# ESP.net
KiCad netlist of a schematic drawn in Altium Designer
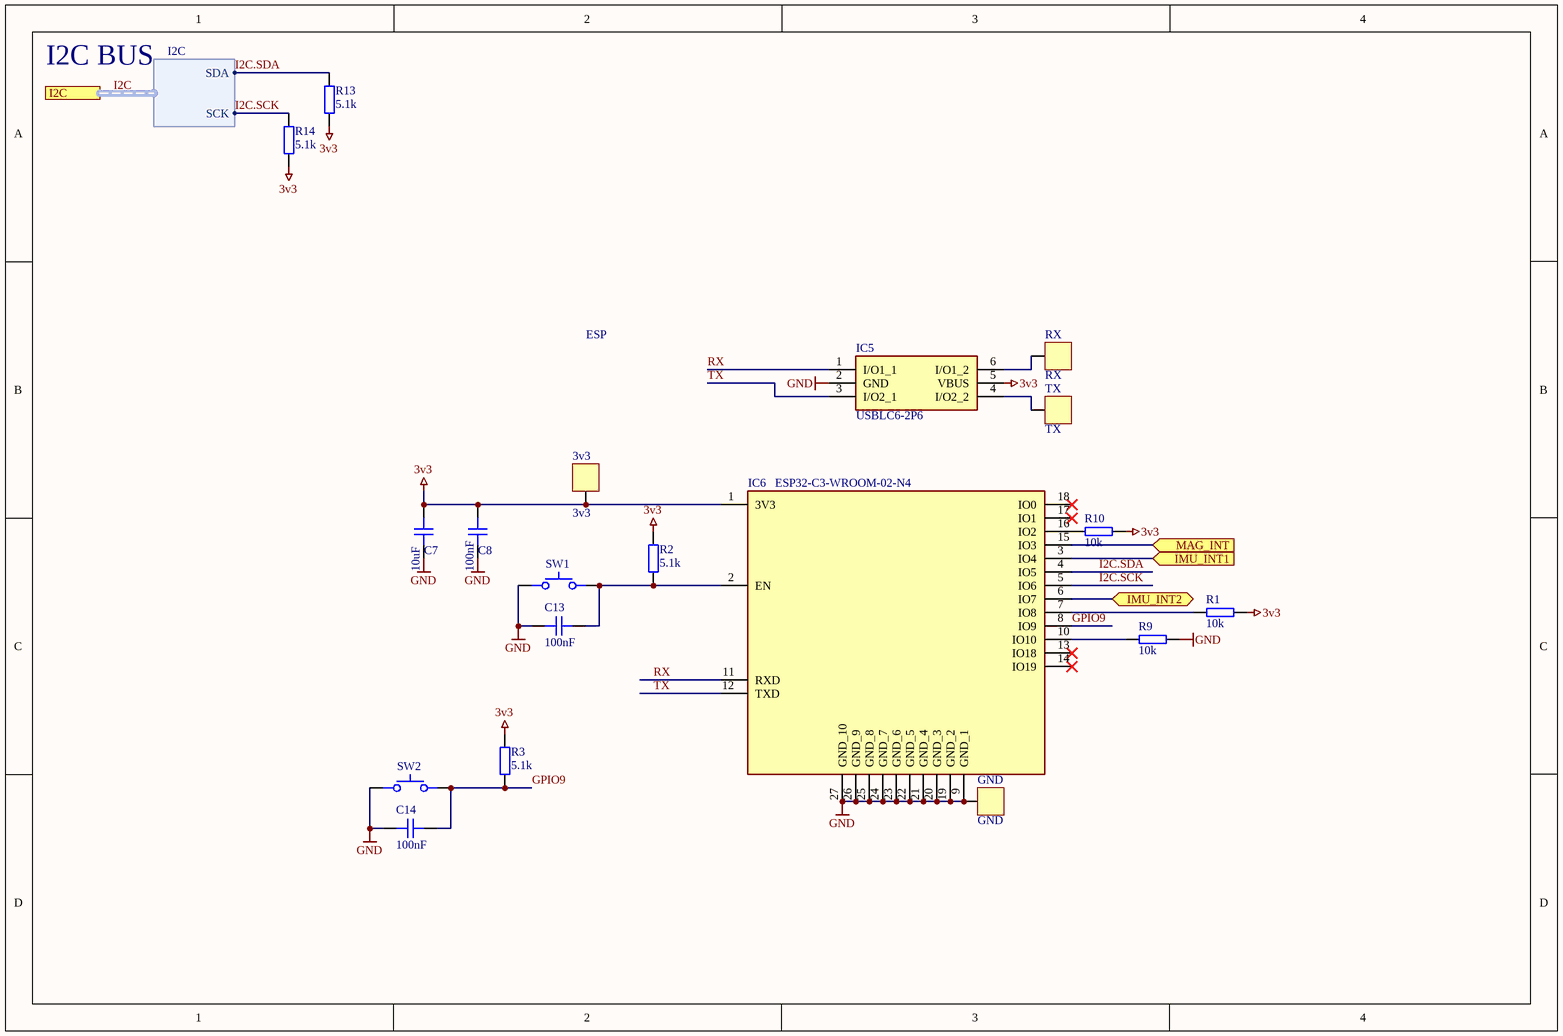
[diagram p0: ESP.SchDoc]

(export (version "E")
  (design (tool "Eeschema 10.0.6"))
  (components
    (comp (ref "3v3")
      (value "3v3")
      (footprint "PAD_SQ_2MM")
      (description "Test Point Square 2mm")
      (libsource (lib "Schematic-Lib-PhilsLab") (part "PAD_SQ_2MM"))
    )
    (comp (ref "C7")
      (value "10uF")
      (footprint "CAP_0402")
      (description "Capacitor SMD 0402 10V")
      (fields (field (name "Comment") "C0402_10V"))
      (libsource (lib "Schematic-Lib-PhilsLab") (part "CAP_0402_10V"))
    )
    (comp (ref "C8")
      (value "100nF")
      (footprint "CAP_0402")
      (description "Capacitor SMD 0402 10V")
      (fields (field (name "Comment") "C0402_10V"))
      (libsource (lib "Schematic-Lib-PhilsLab") (part "CAP_0402_10V"))
    )
    (comp (ref "C13")
      (value "100nF")
      (footprint "CAP_0402")
      (description "Capacitor SMD 0402 10V")
      (fields (field (name "Comment") "C0402_10V"))
      (libsource (lib "Schematic-Lib-PhilsLab") (part "CAP_0402_10V"))
    )
    (comp (ref "C14")
      (value "100nF")
      (footprint "CAP_0402")
      (description "Capacitor SMD 0402 10V")
      (fields (field (name "Comment") "C0402_10V"))
      (libsource (lib "Schematic-Lib-PhilsLab") (part "CAP_0402_10V"))
    )
    (comp (ref "GND")
      (value "GND")
      (footprint "PAD_SQ_2MM")
      (description "Test Point Square 2mm")
      (libsource (lib "") (part "PAD_SQ_2MM_1"))
    )
    (comp (ref "IC5")
      (value "USBLC6-2P6")
      (footprint "Footprint-Lib-PhilsLab:USBLC62P6")
      (description "Integrated Circuit")
      (fields (field (name "MOUSER PART NUMBER") "511-USBLC6-2P6"))
      (libsource (lib "Schematic-Lib-PhilsLab") (part "USBLC6-2P6"))
    )
    (comp (ref "IC6")
      (value "ESP32-C3-WROOM-02-N4")
      (footprint "ESP32C3WROOM02N4")
      (description "Multiprotocol Modules SMD module, ESP32-C3, 4MB SPI flash, PCB antenna, -40 C +85 C")
      (libsource (lib "altium-lib") (part "ESP32-C3-WROOM-02-N4"))
    )
    (comp (ref "R1")
      (value "10k")
      (footprint "RES 0402/1005")
      (description "RES SMD 10k OHM 5% 1/16W 0402")
      (fields (field (name "TOLERANCE") "5%") (field (name "MANUFACTURER PART NUMBER") "CRCW040210K0JNTDBC"))
      (libsource (lib "altium-lib") (part "Resistor"))
    )
    (comp (ref "R2")
      (value "5.1k")
      (footprint "RES_0402")
      (description "Resistor SMD 0402")
      (fields (field (name "Comment") "R0402"))
      (libsource (lib "Schematic-Lib-PhilsLab") (part "RES_0402"))
    )
    (comp (ref "R3")
      (value "5.1k")
      (footprint "RES_0402")
      (description "Resistor SMD 0402")
      (fields (field (name "Comment") "R0402"))
      (libsource (lib "Schematic-Lib-PhilsLab") (part "RES_0402"))
    )
    (comp (ref "R9")
      (value "10k")
      (footprint "RES 0402/1005")
      (description "RES SMD 10k OHM 5% 1/16W 0402")
      (fields (field (name "TOLERANCE") "5%") (field (name "MANUFACTURER PART NUMBER") "CRCW040210K0JNTDBC"))
      (libsource (lib "altium-lib") (part "Resistor"))
    )
    (comp (ref "R10")
      (value "10k")
      (footprint "RES 0402/1005")
      (description "RES SMD 10k OHM 5% 1/16W 0402")
      (fields (field (name "TOLERANCE") "5%") (field (name "MANUFACTURER PART NUMBER") "CRCW040210K0JNTDBC"))
      (libsource (lib "altium-lib") (part "Resistor"))
    )
    (comp (ref "R13")
      (value "5.1k")
      (footprint "RES_0402")
      (description "Resistor SMD 0402")
      (fields (field (name "Comment") "R0402"))
      (libsource (lib "Schematic-Lib-PhilsLab") (part "RES_0402"))
    )
    (comp (ref "R14")
      (value "5.1k")
      (footprint "RES_0402")
      (description "Resistor SMD 0402")
      (fields (field (name "Comment") "R0402"))
      (libsource (lib "Schematic-Lib-PhilsLab") (part "RES_0402"))
    )
    (comp (ref "RX")
      (value "RX")
      (footprint "PAD_SQ_2MM")
      (description "Test Point Square 2mm")
      (libsource (lib "") (part "PAD_SQ_2MM_1"))
    )
    (comp (ref "SW1")
      (value "SKRPANE010")
      (footprint "SKRPANE010")
      (description "Tactile Switch SMD SPST")
      (fields (field (name "MANUFACTURER") "Alps Alpine"))
      (libsource (lib "Schematic-Lib-PhilsLab") (part "SKRPANE010"))
    )
    (comp (ref "SW2")
      (value "SKRPANE010")
      (footprint "SKRPANE010")
      (description "Tactile Switch SMD SPST")
      (fields (field (name "MANUFACTURER") "Alps Alpine"))
      (libsource (lib "Schematic-Lib-PhilsLab") (part "SKRPANE010"))
    )
    (comp (ref "TX")
      (value "TX")
      (footprint "PAD_SQ_2MM")
      (description "Test Point Square 2mm")
      (libsource (lib "") (part "PAD_SQ_2MM_1"))
    )
  )
  (nets
    (net (code "2") (name "/GPIO9") (class "Default")
      (node (ref "C14") (pin "1") (pinfunction "1_1") (pintype "passive"))
      (node (ref "IC6") (pin "8") (pinfunction "IO9_8") (pintype "passive"))
      (node (ref "R3") (pin "1") (pinfunction "1_1") (pintype "passive"))
      (node (ref "SW2") (pin "34") (pintype "passive"))
    )
    (net (code "3") (name "/I2C.SCK") (class "Default")
      (node (ref "IC6") (pin "5") (pinfunction "IO6_5") (pintype "passive"))
      (node (ref "R14") (pin "1") (pinfunction "1_1") (pintype "passive"))
    )
    (net (code "4") (name "/I2C.SDA") (class "Default")
      (node (ref "IC6") (pin "4") (pinfunction "IO5_4") (pintype "passive"))
      (node (ref "R13") (pin "1") (pinfunction "1_1") (pintype "passive"))
    )
    (net (code "6") (name "/IMU_INT1") (class "Default")
      (node (ref "IC6") (pin "3") (pinfunction "IO4_3") (pintype "passive"))
    )
    (net (code "7") (name "/IMU_INT2") (class "Default")
      (node (ref "IC6") (pin "6") (pinfunction "IO7_6") (pintype "passive"))
    )
    (net (code "8") (name "/MAG_INT") (class "Default")
      (node (ref "IC6") (pin "15") (pinfunction "IO3_15") (pintype "passive"))
    )
    (net (code "9") (name "/RX") (class "Default")
      (node (ref "IC5") (pin "1") (pinfunction "I/O1_1_1") (pintype "passive"))
      (node (ref "IC6") (pin "11") (pinfunction "RXD_11") (pintype "passive"))
    )
    (net (code "10") (name "/TX") (class "Default")
      (node (ref "IC5") (pin "3") (pinfunction "I/O2_1_3") (pintype "passive"))
      (node (ref "IC6") (pin "12") (pinfunction "TXD_12") (pintype "passive"))
    )
    (net (code "11") (name "3v3") (class "Default")
      (node (ref "3v3") (pin "1") (pinfunction "1_1") (pintype "passive"))
      (node (ref "C7") (pin "2") (pinfunction "2_2") (pintype "passive"))
      (node (ref "C8") (pin "2") (pinfunction "2_2") (pintype "passive"))
      (node (ref "IC5") (pin "5") (pinfunction "VBUS_5") (pintype "passive"))
      (node (ref "IC6") (pin "1") (pinfunction "3V3_1") (pintype "passive"))
      (node (ref "R1") (pin "2") (pinfunction "2_2") (pintype "passive"))
      (node (ref "R10") (pin "2") (pinfunction "2_2") (pintype "passive"))
      (node (ref "R13") (pin "2") (pinfunction "2_2") (pintype "passive"))
      (node (ref "R14") (pin "2") (pinfunction "2_2") (pintype "passive"))
      (node (ref "R2") (pin "2") (pinfunction "2_2") (pintype "passive"))
      (node (ref "R3") (pin "2") (pinfunction "2_2") (pintype "passive"))
    )
    (net (code "12") (name "GND") (class "Default")
      (node (ref "C13") (pin "2") (pinfunction "2_2") (pintype "passive"))
      (node (ref "C14") (pin "2") (pinfunction "2_2") (pintype "passive"))
      (node (ref "C7") (pin "1") (pinfunction "1_1") (pintype "passive"))
      (node (ref "C8") (pin "1") (pinfunction "1_1") (pintype "passive"))
      (node (ref "GND") (pin "1") (pinfunction "1_1") (pintype "passive"))
      (node (ref "IC5") (pin "2") (pinfunction "GND_2") (pintype "passive"))
      (node (ref "IC6") (pin "19") (pinfunction "GND_2_19") (pintype "passive"))
      (node (ref "IC6") (pin "20") (pinfunction "GND_3_20") (pintype "passive"))
      (node (ref "IC6") (pin "21") (pinfunction "GND_4_21") (pintype "passive"))
      (node (ref "IC6") (pin "22") (pinfunction "GND_5_22") (pintype "passive"))
      (node (ref "IC6") (pin "23") (pinfunction "GND_6_23") (pintype "passive"))
      (node (ref "IC6") (pin "24") (pinfunction "GND_7_24") (pintype "passive"))
      (node (ref "IC6") (pin "25") (pinfunction "GND_8_25") (pintype "passive"))
      (node (ref "IC6") (pin "26") (pinfunction "GND_9_26") (pintype "passive"))
      (node (ref "IC6") (pin "27") (pinfunction "GND_10_27") (pintype "passive"))
      (node (ref "IC6") (pin "9") (pinfunction "GND_1_9") (pintype "passive"))
      (node (ref "R9") (pin "2") (pinfunction "2_2") (pintype "passive"))
      (node (ref "SW1") (pin "12") (pintype "passive"))
      (node (ref "SW2") (pin "12") (pintype "passive"))
    )
    (net (code "13") (name "Net-(IC5-I{slash}O1_2)") (class "Default")
      (node (ref "IC5") (pin "6") (pinfunction "I/O1_2_6") (pintype "passive"))
      (node (ref "RX") (pin "1") (pinfunction "1_1") (pintype "passive"))
    )
    (net (code "14") (name "Net-(IC5-I{slash}O2_2)") (class "Default")
      (node (ref "IC5") (pin "4") (pinfunction "I/O2_2_4") (pintype "passive"))
      (node (ref "TX") (pin "1") (pinfunction "1_1") (pintype "passive"))
    )
    (net (code "15") (name "Net-(IC6-EN)") (class "Default")
      (node (ref "C13") (pin "1") (pinfunction "1_1") (pintype "passive"))
      (node (ref "IC6") (pin "2") (pinfunction "EN_2") (pintype "passive"))
      (node (ref "R2") (pin "1") (pinfunction "1_1") (pintype "passive"))
      (node (ref "SW1") (pin "34") (pintype "passive"))
    )
    (net (code "16") (name "Net-(IC6-IO2)") (class "Default")
      (node (ref "IC6") (pin "16") (pinfunction "IO2_16") (pintype "passive"))
      (node (ref "R10") (pin "1") (pinfunction "1_1") (pintype "passive"))
    )
    (net (code "17") (name "Net-(IC6-IO8)") (class "Default")
      (node (ref "IC6") (pin "7") (pinfunction "IO8_7") (pintype "passive"))
      (node (ref "R1") (pin "1") (pinfunction "1_1") (pintype "passive"))
    )
    (net (code "18") (name "Net-(IC6-IO10)") (class "Default")
      (node (ref "IC6") (pin "10") (pinfunction "IO10_10") (pintype "passive"))
      (node (ref "R9") (pin "1") (pinfunction "1_1") (pintype "passive"))
    )
    (net (code "19") (name "unconnected-(IC6-IO0-Pad18)") (class "Default")
      (node (ref "IC6") (pin "18") (pinfunction "IO0_18") (pintype "passive+no_connect"))
    )
    (net (code "20") (name "unconnected-(IC6-IO1-Pad17)") (class "Default")
      (node (ref "IC6") (pin "17") (pinfunction "IO1_17") (pintype "passive+no_connect"))
    )
    (net (code "21") (name "unconnected-(IC6-IO18-Pad13)") (class "Default")
      (node (ref "IC6") (pin "13") (pinfunction "IO18_13") (pintype "passive+no_connect"))
    )
    (net (code "22") (name "unconnected-(IC6-IO19-Pad14)") (class "Default")
      (node (ref "IC6") (pin "14") (pinfunction "IO19_14") (pintype "passive+no_connect"))
    )
  )
)
